# untitled.net
KiCad netlist of a schematic drawn in EAGLE
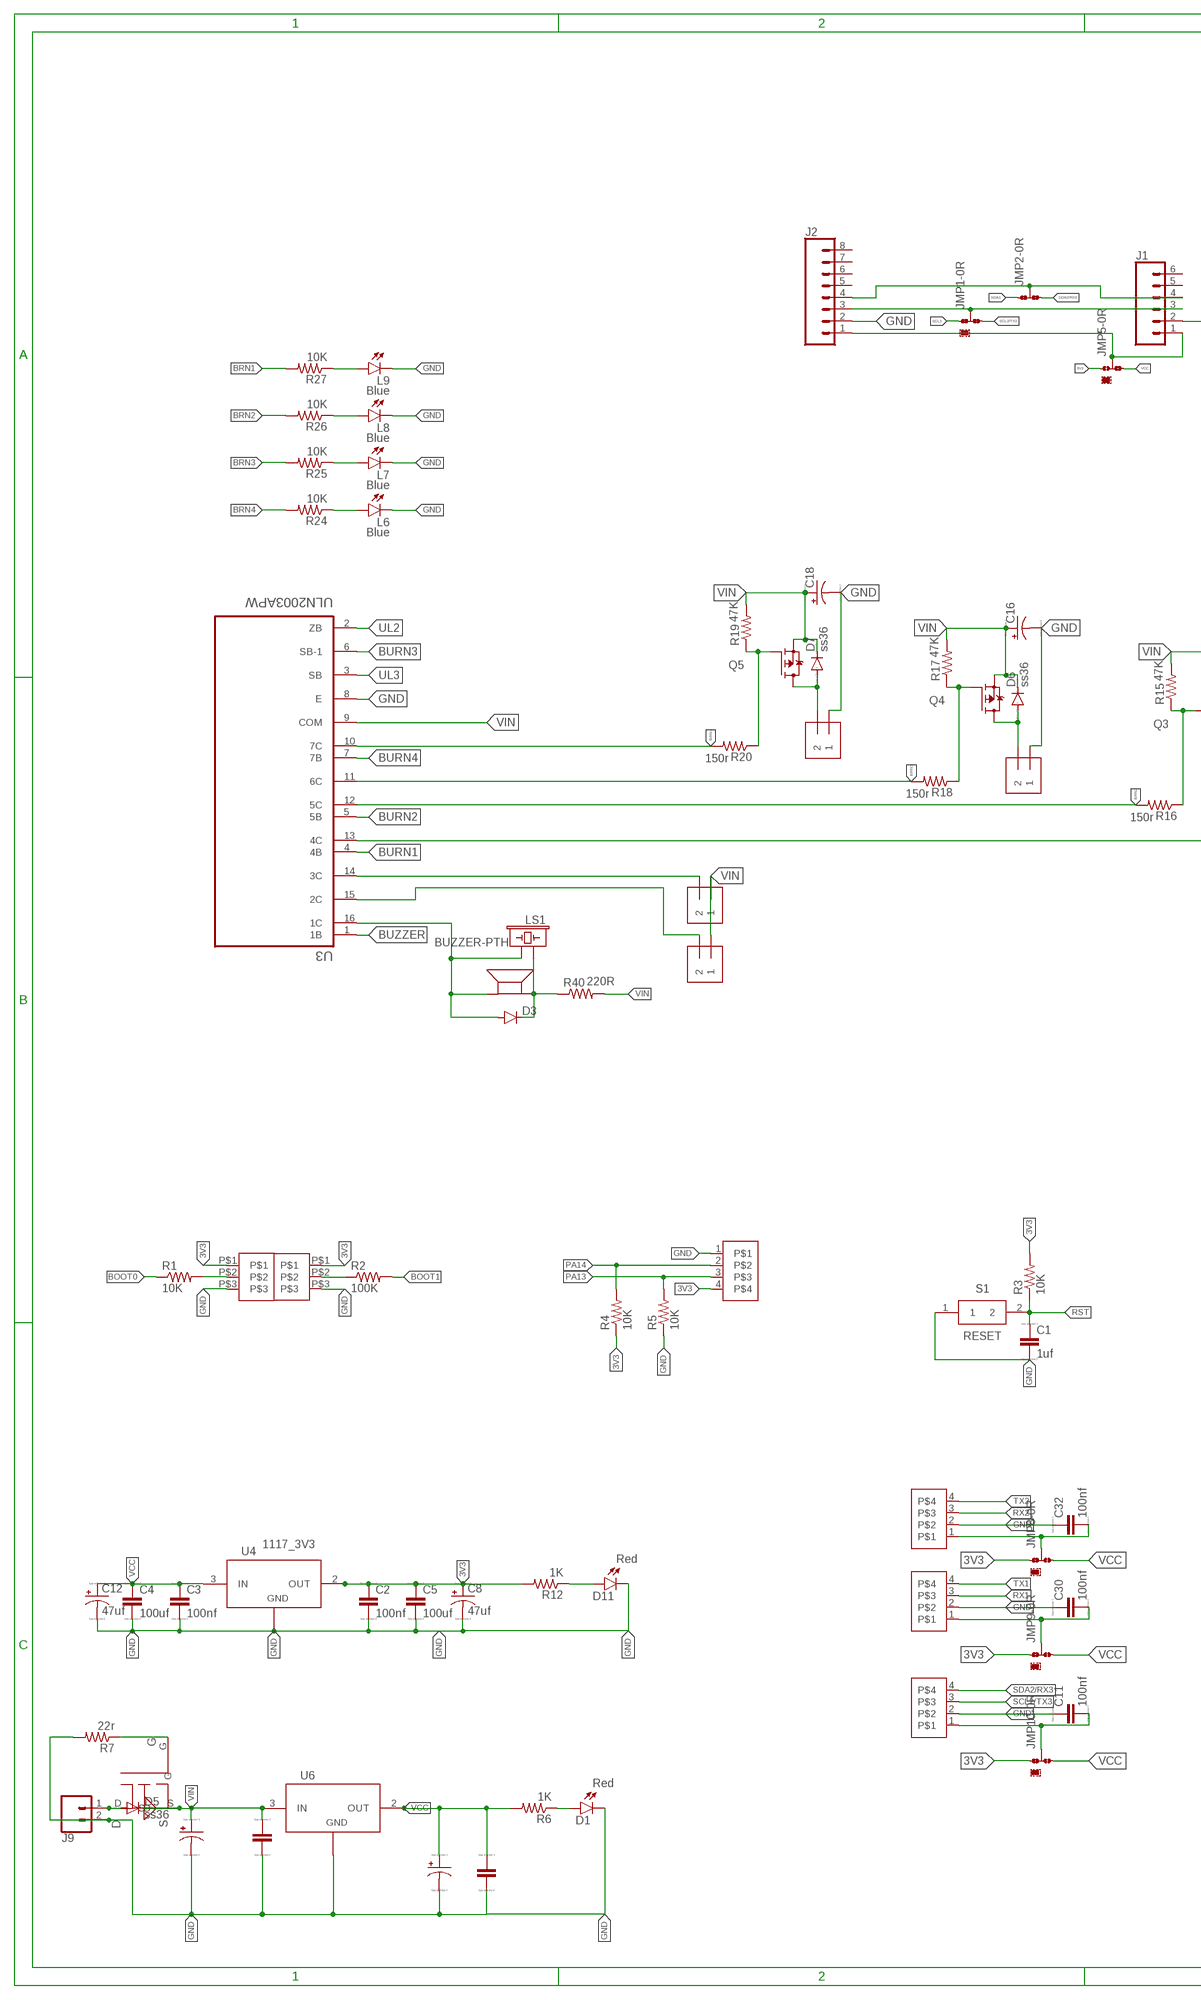
[diagram p0: schematic, sheet 1, part 1 of 2]
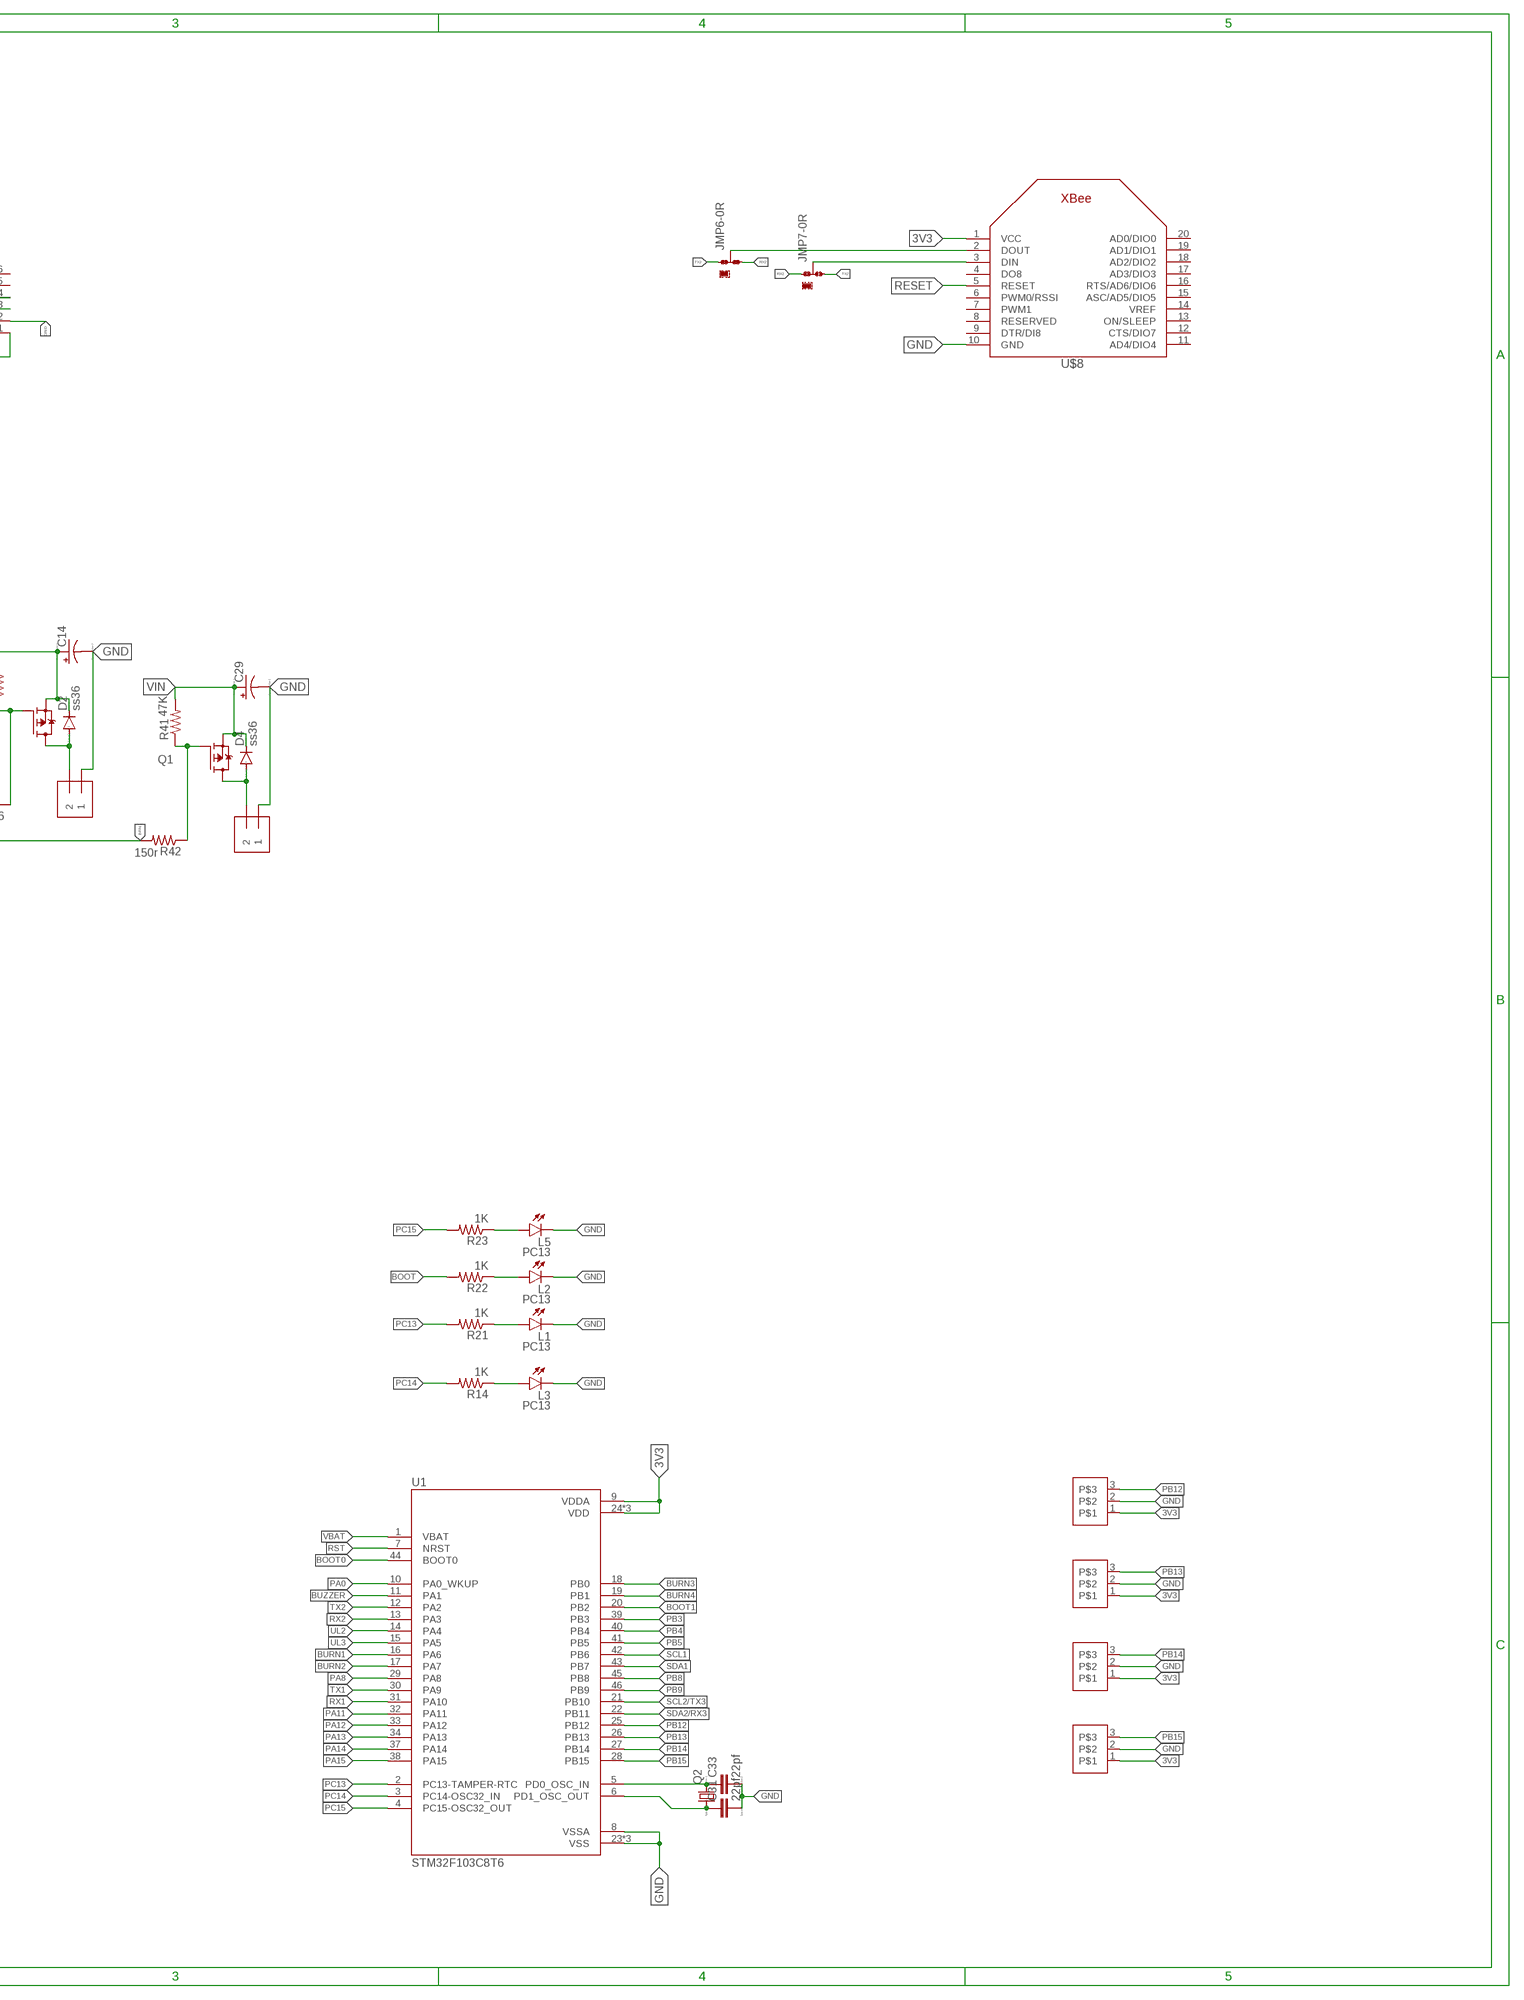
[diagram p1: schematic, sheet 1, part 2 of 2]

(export (version "E")
  (design (tool "Eeschema 10.0.6"))
  (components
    (comp (ref "C1")
      (value "1uf")
      (footprint "eagle-import:C0603")
      (libsource (lib "eagle-import") (part "CAPACITOR_CER4"))
    )
    (comp (ref "C2")
      (value "100nf")
      (footprint "eagle-import:C0603")
      (libsource (lib "eagle-import") (part "CAPACITOR_CER4"))
    )
    (comp (ref "C3")
      (value "100nf")
      (footprint "eagle-import:C0603")
      (libsource (lib "eagle-import") (part "CAPACITOR_CER4"))
    )
    (comp (ref "C4")
      (value "100uf")
      (footprint "eagle-import:C1210")
      (libsource (lib "eagle-import") (part "CAPACITOR_CER9"))
    )
    (comp (ref "C5")
      (value "100uf")
      (footprint "eagle-import:C1210")
      (libsource (lib "eagle-import") (part "CAPACITOR_CER9"))
    )
    (comp (ref "C6")
      (value "100nf")
      (footprint "eagle-import:C0603")
      (libsource (lib "eagle-import") (part "CAPACITOR_CER4"))
    )
    (comp (ref "C7")
      (value "100uf")
      (footprint "eagle-import:PANASONIC_D")
      (libsource (lib "eagle-import") (part "CAPACITOR_POLD"))
    )
    (comp (ref "C8")
      (value "47uf")
      (footprint "eagle-import:PANASONIC_C")
      (libsource (lib "eagle-import") (part "CAPACITOR_POLC"))
    )
    (comp (ref "C9")
      (value "100nf")
      (footprint "eagle-import:C0603")
      (libsource (lib "eagle-import") (part "CAPACITOR_CER4"))
    )
    (comp (ref "C10")
      (value "100uf")
      (footprint "eagle-import:PANASONIC_D")
      (libsource (lib "eagle-import") (part "CAPACITOR_POLD"))
    )
    (comp (ref "C11")
      (value "100nf")
      (footprint "eagle-import:C0603")
      (libsource (lib "eagle-import") (part "CAPACITOR_CER4"))
    )
    (comp (ref "C12")
      (value "47uf")
      (footprint "eagle-import:PANASONIC_C")
      (libsource (lib "eagle-import") (part "CAPACITOR_POLC"))
    )
    (comp (ref "C14")
      (value "CAPACITOR_POLC")
      (footprint "eagle-import:PANASONIC_C")
      (libsource (lib "eagle-import") (part "CAPACITOR_POLC"))
    )
    (comp (ref "C16")
      (value "CAPACITOR_POLC")
      (footprint "eagle-import:PANASONIC_C")
      (libsource (lib "eagle-import") (part "CAPACITOR_POLC"))
    )
    (comp (ref "C18")
      (value "CAPACITOR_POLC")
      (footprint "eagle-import:PANASONIC_C")
      (libsource (lib "eagle-import") (part "CAPACITOR_POLC"))
    )
    (comp (ref "C29")
      (value "CAPACITOR_POLC")
      (footprint "eagle-import:PANASONIC_C")
      (libsource (lib "eagle-import") (part "CAPACITOR_POLC"))
    )
    (comp (ref "C30")
      (value "100nf")
      (footprint "eagle-import:C0603")
      (libsource (lib "eagle-import") (part "CAPACITOR_CER4"))
    )
    (comp (ref "C31")
      (value "22pf")
      (footprint "eagle-import:C0603")
      (libsource (lib "eagle-import") (part "CAPACITOR_CER4"))
    )
    (comp (ref "C32")
      (value "100nf")
      (footprint "eagle-import:C0603")
      (libsource (lib "eagle-import") (part "CAPACITOR_CER4"))
    )
    (comp (ref "C33")
      (value "22pf")
      (footprint "eagle-import:C0603")
      (libsource (lib "eagle-import") (part "CAPACITOR_CER4"))
    )
    (comp (ref "D1")
      (value "Red")
      (footprint "eagle-import:0603_LED_GREEN")
      (libsource (lib "eagle-import") (part "LED0603_R"))
    )
    (comp (ref "D2")
      (value "ss36")
      (footprint "eagle-import:DO-214AC")
      (libsource (lib "eagle-import") (part "DIODEAC2"))
    )
    (comp (ref "D3")
      (value "DIODESOD")
      (footprint "eagle-import:SOD-323")
      (libsource (lib "eagle-import") (part "DIODESOD"))
    )
    (comp (ref "D4")
      (value "ss36")
      (footprint "eagle-import:DO-214AC")
      (libsource (lib "eagle-import") (part "DIODEAC2"))
    )
    (comp (ref "D5")
      (value "ss36")
      (footprint "eagle-import:DO-214AC")
      (libsource (lib "eagle-import") (part "DIODEAC2"))
    )
    (comp (ref "D6")
      (value "ss36")
      (footprint "eagle-import:DO-214AC")
      (libsource (lib "eagle-import") (part "DIODEAC2"))
    )
    (comp (ref "D7")
      (value "ss36")
      (footprint "eagle-import:DO-214AC")
      (libsource (lib "eagle-import") (part "DIODEAC2"))
    )
    (comp (ref "D11")
      (value "Red")
      (footprint "eagle-import:0603_LED_GREEN")
      (libsource (lib "eagle-import") (part "LED0603_R"))
    )
    (comp (ref "J1")
      (value "CONN_06NO_SILK_NO_POP")
      (footprint "eagle-import:1X06_NO_SILK")
      (libsource (lib "eagle-import") (part "CONN_06NO_SILK_NO_POP"))
    )
    (comp (ref "J2")
      (value "CONN_08NO_SILK_FEMALE_PTH")
      (footprint "eagle-import:1X08_NO_SILK")
      (libsource (lib "eagle-import") (part "CONN_08NO_SILK_FEMALE_PTH"))
    )
    (comp (ref "J9")
      (value "CONN_025MM")
      (footprint "eagle-import:SCREWTERMINAL-5MM-2")
      (libsource (lib "eagle-import") (part "CONN_025MM"))
    )
    (comp (ref "JMP1")
      (value "0R-JUMPA")
      (footprint "eagle-import:A0R-JMP")
      (libsource (lib "eagle-import") (part "0R-JUMPA"))
    )
    (comp (ref "JMP2")
      (value "0R-JUMPA")
      (footprint "eagle-import:A0R-JMP")
      (libsource (lib "eagle-import") (part "0R-JUMPA"))
    )
    (comp (ref "JMP5")
      (value "0R-JUMPA")
      (footprint "eagle-import:A0R-JMP")
      (libsource (lib "eagle-import") (part "0R-JUMPA"))
    )
    (comp (ref "JMP6")
      (value "0R-JUMPA")
      (footprint "eagle-import:A0R-JMP")
      (libsource (lib "eagle-import") (part "0R-JUMPA"))
    )
    (comp (ref "JMP7")
      (value "0R-JUMPA")
      (footprint "eagle-import:A0R-JMP")
      (libsource (lib "eagle-import") (part "0R-JUMPA"))
    )
    (comp (ref "JMP8")
      (value "0R-JUMPA")
      (footprint "eagle-import:A0R-JMP")
      (libsource (lib "eagle-import") (part "0R-JUMPA"))
    )
    (comp (ref "JMP9")
      (value "0R-JUMPA")
      (footprint "eagle-import:A0R-JMP")
      (libsource (lib "eagle-import") (part "0R-JUMPA"))
    )
    (comp (ref "JMP10")
      (value "0R-JUMPA")
      (footprint "eagle-import:A0R-JMP")
      (libsource (lib "eagle-import") (part "0R-JUMPA"))
    )
    (comp (ref "L1")
      (value "PC13")
      (footprint "eagle-import:0603_LED_GREEN")
      (libsource (lib "eagle-import") (part "LED0603_R"))
    )
    (comp (ref "L2")
      (value "PC13")
      (footprint "eagle-import:0603_LED_GREEN")
      (libsource (lib "eagle-import") (part "LED0603_R"))
    )
    (comp (ref "L3")
      (value "PC13")
      (footprint "eagle-import:0603_LED_GREEN")
      (libsource (lib "eagle-import") (part "LED0603_R"))
    )
    (comp (ref "L5")
      (value "PC13")
      (footprint "eagle-import:0603_LED_GREEN")
      (libsource (lib "eagle-import") (part "LED0603_R"))
    )
    (comp (ref "L6")
      (value "Blue")
      (footprint "eagle-import:0603_LED_GREEN")
      (libsource (lib "eagle-import") (part "LED0603_R"))
    )
    (comp (ref "L7")
      (value "Blue")
      (footprint "eagle-import:0603_LED_GREEN")
      (libsource (lib "eagle-import") (part "LED0603_R"))
    )
    (comp (ref "L8")
      (value "Blue")
      (footprint "eagle-import:0603_LED_GREEN")
      (libsource (lib "eagle-import") (part "LED0603_R"))
    )
    (comp (ref "L9")
      (value "Blue")
      (footprint "eagle-import:0603_LED_GREEN")
      (libsource (lib "eagle-import") (part "LED0603_R"))
    )
    (comp (ref "LS1")
      (value "BUZZER-PTH")
      (footprint "eagle-import:BUZZER-12MM")
      (libsource (lib "eagle-import") (part "BUZZER-PTH"))
    )
    (comp (ref "Q1")
      (value "FDD4141TO252")
      (footprint "eagle-import:TO252")
      (libsource (lib "eagle-import") (part "FDD4141TO252"))
    )
    (comp (ref "Q2")
      (value "CRYSTALHC49U-V")
      (footprint "eagle-import:HC49U-V")
      (libsource (lib "eagle-import") (part "CRYSTALHC49U-V"))
    )
    (comp (ref "Q3")
      (value "FDD4141TO252")
      (footprint "eagle-import:TO252")
      (libsource (lib "eagle-import") (part "FDD4141TO252"))
    )
    (comp (ref "Q4")
      (value "FDD4141TO252")
      (footprint "eagle-import:TO252")
      (libsource (lib "eagle-import") (part "FDD4141TO252"))
    )
    (comp (ref "Q5")
      (value "FDD4141TO252")
      (footprint "eagle-import:TO252")
      (libsource (lib "eagle-import") (part "FDD4141TO252"))
    )
    (comp (ref "Q6")
      (value "AON7401")
      (footprint "eagle-import:DFN-8_3X3")
      (libsource (lib "eagle-import") (part "AON7401"))
    )
    (comp (ref "R1")
      (value "10K")
      (footprint "eagle-import:R0603")
      (libsource (lib "eagle-import") (part "RESISTOR0603"))
    )
    (comp (ref "R2")
      (value "100K")
      (footprint "eagle-import:R0603")
      (libsource (lib "eagle-import") (part "RESISTOR0603"))
    )
    (comp (ref "R3")
      (value "10K")
      (footprint "eagle-import:R0603")
      (libsource (lib "eagle-import") (part "RESISTOR0603"))
    )
    (comp (ref "R4")
      (value "10K")
      (footprint "eagle-import:R0603")
      (libsource (lib "eagle-import") (part "RESISTOR0603"))
    )
    (comp (ref "R5")
      (value "10K")
      (footprint "eagle-import:R0603")
      (libsource (lib "eagle-import") (part "RESISTOR0603"))
    )
    (comp (ref "R6")
      (value "1K")
      (footprint "eagle-import:R0603")
      (libsource (lib "eagle-import") (part "RESISTOR0603"))
    )
    (comp (ref "R7")
      (value "22r")
      (footprint "eagle-import:R0603")
      (libsource (lib "eagle-import") (part "RESISTOR0603"))
    )
    (comp (ref "R12")
      (value "1K")
      (footprint "eagle-import:R0603")
      (libsource (lib "eagle-import") (part "RESISTOR0603"))
    )
    (comp (ref "R14")
      (value "1K")
      (footprint "eagle-import:R0603")
      (libsource (lib "eagle-import") (part "RESISTOR0603"))
    )
    (comp (ref "R15")
      (value "47K")
      (footprint "eagle-import:R0603")
      (libsource (lib "eagle-import") (part "RESISTOR0603"))
    )
    (comp (ref "R16")
      (value "150r")
      (footprint "eagle-import:R0603")
      (libsource (lib "eagle-import") (part "RESISTOR0603"))
    )
    (comp (ref "R17")
      (value "47K")
      (footprint "eagle-import:R0603")
      (libsource (lib "eagle-import") (part "RESISTOR0603"))
    )
    (comp (ref "R18")
      (value "150r")
      (footprint "eagle-import:R0603")
      (libsource (lib "eagle-import") (part "RESISTOR0603"))
    )
    (comp (ref "R19")
      (value "47K")
      (footprint "eagle-import:R0603")
      (libsource (lib "eagle-import") (part "RESISTOR0603"))
    )
    (comp (ref "R20")
      (value "150r")
      (footprint "eagle-import:R0603")
      (libsource (lib "eagle-import") (part "RESISTOR0603"))
    )
    (comp (ref "R21")
      (value "1K")
      (footprint "eagle-import:R0603")
      (libsource (lib "eagle-import") (part "RESISTOR0603"))
    )
    (comp (ref "R22")
      (value "1K")
      (footprint "eagle-import:R0603")
      (libsource (lib "eagle-import") (part "RESISTOR0603"))
    )
    (comp (ref "R23")
      (value "1K")
      (footprint "eagle-import:R0603")
      (libsource (lib "eagle-import") (part "RESISTOR0603"))
    )
    (comp (ref "R24")
      (value "10K")
      (footprint "eagle-import:R0603")
      (libsource (lib "eagle-import") (part "RESISTOR0603"))
    )
    (comp (ref "R25")
      (value "10K")
      (footprint "eagle-import:R0603")
      (libsource (lib "eagle-import") (part "RESISTOR0603"))
    )
    (comp (ref "R26")
      (value "10K")
      (footprint "eagle-import:R0603")
      (libsource (lib "eagle-import") (part "RESISTOR0603"))
    )
    (comp (ref "R27")
      (value "10K")
      (footprint "eagle-import:R0603")
      (libsource (lib "eagle-import") (part "RESISTOR0603"))
    )
    (comp (ref "R40")
      (value "220R")
      (footprint "eagle-import:R0603")
      (libsource (lib "eagle-import") (part "RESISTOR0603"))
    )
    (comp (ref "R41")
      (value "47K")
      (footprint "eagle-import:R0603")
      (libsource (lib "eagle-import") (part "RESISTOR0603"))
    )
    (comp (ref "R42")
      (value "150r")
      (footprint "eagle-import:R0603")
      (libsource (lib "eagle-import") (part "RESISTOR0603"))
    )
    (comp (ref "S1")
      (value "RESET")
      (footprint "eagle-import:SKRK")
      (fields (field (name "MF") "ALPS") (field (name "MP") "SKRKAEE010"))
      (libsource (lib "eagle-import") (part "SKRKAEE010"))
    )
    (comp (ref "U$1")
      (value "FML_1X32MM")
      (footprint "eagle-import:1X3_2MM")
      (libsource (lib "eagle-import") (part "FML_1X32MM"))
    )
    (comp (ref "U$2")
      (value "FML_1X32MM")
      (footprint "eagle-import:1X3_2MM")
      (libsource (lib "eagle-import") (part "FML_1X32MM"))
    )
    (comp (ref "U$3")
      (value "FML_1X4")
      (footprint "eagle-import:HDRVR4W64P254_1X4_1016X240X800B")
      (libsource (lib "eagle-import") (part "FML_1X4"))
    )
    (comp (ref "U$4")
      (value "1X2")
      (footprint "eagle-import:1X2")
      (libsource (lib "eagle-import") (part "1X2"))
    )
    (comp (ref "U$5")
      (value "1X2")
      (footprint "eagle-import:1X2")
      (libsource (lib "eagle-import") (part "1X2"))
    )
    (comp (ref "U$6")
      (value "1X2")
      (footprint "eagle-import:1X2")
      (libsource (lib "eagle-import") (part "1X2"))
    )
    (comp (ref "U$7")
      (value "FML_1X4")
      (footprint "eagle-import:HDRVR4W64P254_1X4_1016X240X800B")
      (libsource (lib "eagle-import") (part "FML_1X4"))
    )
    (comp (ref "U$8")
      (value "XBEE")
      (footprint "eagle-import:XBEE")
      (libsource (lib "eagle-import") (part "XBEE"))
    )
    (comp (ref "U$9")
      (value "Z_STOP")
      (footprint "eagle-import:HDRVR3W64P254_1X3_762X240X800B")
      (libsource (lib "eagle-import") (part "FML_1X3"))
    )
    (comp (ref "U$11")
      (value "FML_1X4")
      (footprint "eagle-import:HDRVR4W64P254_1X4_1016X240X800B")
      (libsource (lib "eagle-import") (part "FML_1X4"))
    )
    (comp (ref "U$12")
      (value "FML_1X4")
      (footprint "eagle-import:HDRVR4W64P254_1X4_1016X240X800B")
      (libsource (lib "eagle-import") (part "FML_1X4"))
    )
    (comp (ref "U$13")
      (value "Z_STOP")
      (footprint "eagle-import:HDRVR3W64P254_1X3_762X240X800B")
      (libsource (lib "eagle-import") (part "FML_1X3"))
    )
    (comp (ref "U$14")
      (value "Y_STOP")
      (footprint "eagle-import:HDRVR3W64P254_1X3_762X240X800B")
      (libsource (lib "eagle-import") (part "FML_1X3"))
    )
    (comp (ref "U$15")
      (value "X_STOP")
      (footprint "eagle-import:HDRVR3W64P254_1X3_762X240X800B")
      (libsource (lib "eagle-import") (part "FML_1X3"))
    )
    (comp (ref "U$19")
      (value "7.5X7.5_BUZZER")
      (footprint "eagle-import:SMD_7.5_BUZZER")
      (libsource (lib "eagle-import") (part "7.5X7.5_BUZZER"))
    )
    (comp (ref "U$20")
      (value "1X2")
      (footprint "eagle-import:1X2")
      (libsource (lib "eagle-import") (part "1X2"))
    )
    (comp (ref "U$21")
      (value "1X2")
      (footprint "eagle-import:1X2")
      (libsource (lib "eagle-import") (part "1X2"))
    )
    (comp (ref "U$22")
      (value "1X2")
      (footprint "eagle-import:1X2")
      (libsource (lib "eagle-import") (part "1X2"))
    )
    (comp (ref "U1")
      (value "STM32F103C8T6")
      (footprint "eagle-import:QFP50P900X900X160-48N")
      (fields (field (name "MF") "STMicroelectronics"))
      (libsource (lib "eagle-import") (part "STM32F103C8T6"))
    )
    (comp (ref "U3")
      (value "ULN2003APW")
      (footprint "eagle-import:SOP65P640X120-16N")
      (fields (field (name "MF") "Texas Instruments"))
      (libsource (lib "eagle-import") (part "ULN2003APW"))
    )
    (comp (ref "U4")
      (value "1117_3V3")
      (footprint "eagle-import:SOT-223")
      (fields
        (field (name "DIGIKEY_PART_NUMBER") "NCP1117ST33T3GOSTR-ND")
        (field (name "MANUFACTURER") "ON Semiconductor")
        (field (name "MPN") "NCP1117ST33T3G")
        (field (name "CREATED_BY") "PCBLayout.com")
      )
      (libsource (lib "eagle-import") (part "NCP1117ST33T3G"))
    )
    (comp (ref "U6")
      (value "1117_3V3")
      (footprint "eagle-import:SOT-223")
      (fields
        (field (name "DIGIKEY_PART_NUMBER") "NCP1117ST33T3GOSTR-ND")
        (field (name "MANUFACTURER") "ON Semiconductor")
        (field (name "MPN") "NCP1117ST33T3G")
        (field (name "CREATED_BY") "PCBLayout.com")
      )
      (libsource (lib "eagle-import") (part "NCP1117ST33T3G"))
    )
  )
  (nets
    (net (code "1") (name "3V3") (class "Default")
      (node (ref "C2") (pin "1") (pinfunction "1_1") (pintype "passive"))
      (node (ref "C5") (pin "1") (pinfunction "1_1") (pintype "passive"))
      (node (ref "C8") (pin "+") (pinfunction "+_+") (pintype "passive"))
      (node (ref "JMP10") (pin "1") (pinfunction "1_1") (pintype "passive"))
      (node (ref "JMP5") (pin "1") (pinfunction "1_1") (pintype "passive"))
      (node (ref "JMP8") (pin "1") (pinfunction "1_1") (pintype "passive"))
      (node (ref "JMP9") (pin "1") (pinfunction "1_1") (pintype "passive"))
      (node (ref "R12") (pin "2") (pinfunction "2_2") (pintype "passive"))
      (node (ref "R3") (pin "2") (pinfunction "2_2") (pintype "passive"))
      (node (ref "R4") (pin "1") (pinfunction "1_1") (pintype "passive"))
      (node (ref "U$1") (pin "P$1") (pinfunction "P$1_P$1") (pintype "bidirectional"))
      (node (ref "U$13") (pin "1") (pinfunction "P$1_1") (pintype "bidirectional"))
      (node (ref "U$14") (pin "1") (pinfunction "P$1_1") (pintype "bidirectional"))
      (node (ref "U$15") (pin "1") (pinfunction "P$1_1") (pintype "bidirectional"))
      (node (ref "U$2") (pin "P$1") (pinfunction "P$1_P$1") (pintype "bidirectional"))
      (node (ref "U$3") (pin "4") (pinfunction "P$4_4") (pintype "bidirectional"))
      (node (ref "U$8") (pin "1") (pinfunction "VCC_1") (pintype "power_in"))
      (node (ref "U$9") (pin "1") (pinfunction "P$1_1") (pintype "bidirectional"))
      (node (ref "U1") (pin "24") (pinfunction "VDD_24") (pintype "power_in"))
      (node (ref "U1") (pin "36") (pinfunction "VDD_36") (pintype "power_in"))
      (node (ref "U1") (pin "48") (pinfunction "VDD_48") (pintype "power_in"))
      (node (ref "U1") (pin "9") (pinfunction "VDDA_9") (pintype "power_in"))
      (node (ref "U4") (pin "2") (pinfunction "OUT_2") (pintype "output"))
      (node (ref "U4") (pin "4") (pinfunction "4_4") (pintype "passive"))
    )
    (net (code "2") (name "BOOT") (class "Default")
      (node (ref "R1") (pin "2") (pinfunction "2_2") (pintype "passive"))
      (node (ref "R22") (pin "2") (pinfunction "2_2") (pintype "passive"))
      (node (ref "U$2") (pin "P$2") (pinfunction "P$2_P$2") (pintype "bidirectional"))
    )
    (net (code "3") (name "BOOT0") (class "Default")
      (node (ref "R1") (pin "1") (pinfunction "1_1") (pintype "passive"))
      (node (ref "U1") (pin "44") (pinfunction "BOOT0_44") (pintype "input"))
    )
    (net (code "4") (name "BOOT1") (class "Default")
      (node (ref "R2") (pin "2") (pinfunction "2_2") (pintype "passive"))
      (node (ref "U1") (pin "20") (pinfunction "PB2_20") (pintype "bidirectional"))
    )
    (net (code "5") (name "BRN1") (class "Default")
      (node (ref "R27") (pin "2") (pinfunction "2_2") (pintype "passive"))
      (node (ref "R42") (pin "2") (pinfunction "2_2") (pintype "passive"))
      (node (ref "U3") (pin "13") (pinfunction "4C_13") (pintype "bidirectional"))
    )
    (net (code "6") (name "BRN2") (class "Default")
      (node (ref "R16") (pin "2") (pinfunction "2_2") (pintype "passive"))
      (node (ref "R26") (pin "2") (pinfunction "2_2") (pintype "passive"))
      (node (ref "U3") (pin "12") (pinfunction "5C_12") (pintype "bidirectional"))
    )
    (net (code "7") (name "BRN3") (class "Default")
      (node (ref "R18") (pin "2") (pinfunction "2_2") (pintype "passive"))
      (node (ref "R25") (pin "2") (pinfunction "2_2") (pintype "passive"))
      (node (ref "U3") (pin "11") (pinfunction "6C_11") (pintype "bidirectional"))
    )
    (net (code "8") (name "BRN4") (class "Default")
      (node (ref "R20") (pin "2") (pinfunction "2_2") (pintype "passive"))
      (node (ref "R24") (pin "2") (pinfunction "2_2") (pintype "passive"))
      (node (ref "U3") (pin "10") (pinfunction "7C_10") (pintype "bidirectional"))
    )
    (net (code "9") (name "BURN1") (class "Default")
      (node (ref "U1") (pin "16") (pinfunction "PA6_16") (pintype "bidirectional"))
      (node (ref "U3") (pin "4") (pinfunction "4B_4") (pintype "bidirectional"))
    )
    (net (code "10") (name "BURN2") (class "Default")
      (node (ref "U1") (pin "17") (pinfunction "PA7_17") (pintype "bidirectional"))
      (node (ref "U3") (pin "5") (pinfunction "5B_5") (pintype "bidirectional"))
    )
    (net (code "11") (name "BURN3") (class "Default")
      (node (ref "U1") (pin "18") (pinfunction "PB0_18") (pintype "bidirectional"))
      (node (ref "U3") (pin "6") (pinfunction "SB-1_6") (pintype "bidirectional"))
    )
    (net (code "12") (name "BURN4") (class "Default")
      (node (ref "U1") (pin "19") (pinfunction "PB1_19") (pintype "bidirectional"))
      (node (ref "U3") (pin "7") (pinfunction "7B_7") (pintype "bidirectional"))
    )
    (net (code "13") (name "BUZZER") (class "Default")
      (node (ref "U1") (pin "11") (pinfunction "PA1_11") (pintype "bidirectional"))
      (node (ref "U3") (pin "1") (pinfunction "1B_1") (pintype "bidirectional"))
    )
    (net (code "14") (name "GND") (class "Default")
      (node (ref "C1") (pin "2") (pinfunction "2_2") (pintype "passive"))
      (node (ref "C10") (pin "-") (pinfunction "-_-") (pintype "passive"))
      (node (ref "C11") (pin "1") (pinfunction "1_1") (pintype "passive"))
      (node (ref "C12") (pin "-") (pinfunction "-_-") (pintype "passive"))
      (node (ref "C14") (pin "-") (pinfunction "-_-") (pintype "passive"))
      (node (ref "C16") (pin "-") (pinfunction "-_-") (pintype "passive"))
      (node (ref "C18") (pin "-") (pinfunction "-_-") (pintype "passive"))
      (node (ref "C2") (pin "2") (pinfunction "2_2") (pintype "passive"))
      (node (ref "C29") (pin "-") (pinfunction "-_-") (pintype "passive"))
      (node (ref "C3") (pin "2") (pinfunction "2_2") (pintype "passive"))
      (node (ref "C30") (pin "1") (pinfunction "1_1") (pintype "passive"))
      (node (ref "C31") (pin "2") (pinfunction "2_2") (pintype "passive"))
      (node (ref "C32") (pin "1") (pinfunction "1_1") (pintype "passive"))
      (node (ref "C33") (pin "2") (pinfunction "2_2") (pintype "passive"))
      (node (ref "C4") (pin "2") (pinfunction "2_2") (pintype "passive"))
      (node (ref "C5") (pin "2") (pinfunction "2_2") (pintype "passive"))
      (node (ref "C6") (pin "2") (pinfunction "2_2") (pintype "passive"))
      (node (ref "C7") (pin "-") (pinfunction "-_-") (pintype "passive"))
      (node (ref "C8") (pin "-") (pinfunction "-_-") (pintype "passive"))
      (node (ref "C9") (pin "2") (pinfunction "2_2") (pintype "passive"))
      (node (ref "D1") (pin "C") (pinfunction "C_C") (pintype "passive"))
      (node (ref "D11") (pin "C") (pinfunction "C_C") (pintype "passive"))
      (node (ref "J1") (pin "2") (pinfunction "2_2") (pintype "passive"))
      (node (ref "J2") (pin "2") (pinfunction "2_2") (pintype "passive"))
      (node (ref "J9") (pin "2") (pinfunction "2_2") (pintype "passive"))
      (node (ref "L1") (pin "C") (pinfunction "C_C") (pintype "passive"))
      (node (ref "L2") (pin "C") (pinfunction "C_C") (pintype "passive"))
      (node (ref "L3") (pin "C") (pinfunction "C_C") (pintype "passive"))
      (node (ref "L5") (pin "C") (pinfunction "C_C") (pintype "passive"))
      (node (ref "L6") (pin "C") (pinfunction "C_C") (pintype "passive"))
      (node (ref "L7") (pin "C") (pinfunction "C_C") (pintype "passive"))
      (node (ref "L8") (pin "C") (pinfunction "C_C") (pintype "passive"))
      (node (ref "L9") (pin "C") (pinfunction "C_C") (pintype "passive"))
      (node (ref "R5") (pin "1") (pinfunction "1_1") (pintype "passive"))
      (node (ref "R7") (pin "2") (pinfunction "2_2") (pintype "passive"))
      (node (ref "S1") (pin "1") (pinfunction "1_1") (pintype "passive"))
      (node (ref "U$1") (pin "P$3") (pinfunction "P$3_P$3") (pintype "bidirectional"))
      (node (ref "U$11") (pin "2") (pinfunction "P$2_2") (pintype "bidirectional"))
      (node (ref "U$12") (pin "2") (pinfunction "P$2_2") (pintype "bidirectional"))
      (node (ref "U$13") (pin "2") (pinfunction "P$2_2") (pintype "bidirectional"))
      (node (ref "U$14") (pin "2") (pinfunction "P$2_2") (pintype "bidirectional"))
      (node (ref "U$15") (pin "2") (pinfunction "P$2_2") (pintype "bidirectional"))
      (node (ref "U$2") (pin "P$3") (pinfunction "P$3_P$3") (pintype "bidirectional"))
      (node (ref "U$21") (pin "P$1") (pinfunction "1_P$1") (pintype "passive"))
      (node (ref "U$3") (pin "1") (pinfunction "P$1_1") (pintype "bidirectional"))
      (node (ref "U$4") (pin "P$1") (pinfunction "1_P$1") (pintype "passive"))
      (node (ref "U$5") (pin "P$1") (pinfunction "1_P$1") (pintype "passive"))
      (node (ref "U$6") (pin "P$1") (pinfunction "1_P$1") (pintype "passive"))
      (node (ref "U$7") (pin "2") (pinfunction "P$2_2") (pintype "bidirectional"))
      (node (ref "U$8") (pin "10") (pinfunction "GND_10") (pintype "power_in"))
      (node (ref "U$9") (pin "2") (pinfunction "P$2_2") (pintype "bidirectional"))
      (node (ref "U1") (pin "23") (pinfunction "VSS_23") (pintype "power_in"))
      (node (ref "U1") (pin "35") (pinfunction "VSS_35") (pintype "power_in"))
      (node (ref "U1") (pin "47") (pinfunction "VSS_47") (pintype "power_in"))
      (node (ref "U1") (pin "8") (pinfunction "VSSA_8") (pintype "power_in"))
      (node (ref "U3") (pin "8") (pinfunction "E_8") (pintype "bidirectional"))
      (node (ref "U4") (pin "1") (pinfunction "ADJ/GND_1") (pintype "power_in"))
      (node (ref "U6") (pin "1") (pinfunction "ADJ/GND_1") (pintype "power_in"))
    )
    (net (code "15") (name "Net-(D1-PadA)") (class "Default")
      (node (ref "D1") (pin "A") (pinfunction "A_A") (pintype "passive"))
      (node (ref "R6") (pin "1") (pinfunction "1_1") (pintype "passive"))
    )
    (net (code "16") (name "Net-(D5-PadA)") (class "Default")
      (node (ref "D5") (pin "A") (pinfunction "A_A") (pintype "passive"))
      (node (ref "J9") (pin "1") (pinfunction "1_1") (pintype "passive"))
      (node (ref "Q6") (pin "D") (pinfunction "D_D") (pintype "bidirectional"))
    )
    (net (code "17") (name "Net-(D11-PadA)") (class "Default")
      (node (ref "D11") (pin "A") (pinfunction "A_A") (pintype "passive"))
      (node (ref "R12") (pin "1") (pinfunction "1_1") (pintype "passive"))
    )
    (net (code "18") (name "Net-(J1-Pad1)") (class "Default")
      (node (ref "J1") (pin "1") (pinfunction "1_1") (pintype "passive"))
      (node (ref "J2") (pin "1") (pinfunction "1_1") (pintype "passive"))
      (node (ref "JMP5") (pin "2") (pinfunction "2_2") (pintype "passive"))
    )
    (net (code "19") (name "Net-(J1-Pad3)") (class "Default")
      (node (ref "J1") (pin "3") (pinfunction "3_3") (pintype "passive"))
      (node (ref "J2") (pin "3") (pinfunction "3_3") (pintype "passive"))
      (node (ref "JMP1") (pin "2") (pinfunction "2_2") (pintype "passive"))
    )
    (net (code "20") (name "Net-(J1-Pad4)") (class "Default")
      (node (ref "J1") (pin "4") (pinfunction "4_4") (pintype "passive"))
      (node (ref "J2") (pin "4") (pinfunction "4_4") (pintype "passive"))
      (node (ref "JMP2") (pin "2") (pinfunction "2_2") (pintype "passive"))
    )
    (net (code "21") (name "Net-(L1-PadA)") (class "Default")
      (node (ref "L1") (pin "A") (pinfunction "A_A") (pintype "passive"))
      (node (ref "R21") (pin "1") (pinfunction "1_1") (pintype "passive"))
    )
    (net (code "22") (name "Net-(L2-PadA)") (class "Default")
      (node (ref "L2") (pin "A") (pinfunction "A_A") (pintype "passive"))
      (node (ref "R22") (pin "1") (pinfunction "1_1") (pintype "passive"))
    )
    (net (code "23") (name "Net-(L3-PadA)") (class "Default")
      (node (ref "L3") (pin "A") (pinfunction "A_A") (pintype "passive"))
      (node (ref "R14") (pin "1") (pinfunction "1_1") (pintype "passive"))
    )
    (net (code "24") (name "Net-(L5-PadA)") (class "Default")
      (node (ref "L5") (pin "A") (pinfunction "A_A") (pintype "passive"))
      (node (ref "R23") (pin "1") (pinfunction "1_1") (pintype "passive"))
    )
    (net (code "25") (name "Net-(L6-PadA)") (class "Default")
      (node (ref "L6") (pin "A") (pinfunction "A_A") (pintype "passive"))
      (node (ref "R24") (pin "1") (pinfunction "1_1") (pintype "passive"))
    )
    (net (code "26") (name "Net-(L7-PadA)") (class "Default")
      (node (ref "L7") (pin "A") (pinfunction "A_A") (pintype "passive"))
      (node (ref "R25") (pin "1") (pinfunction "1_1") (pintype "passive"))
    )
    (net (code "27") (name "Net-(L8-PadA)") (class "Default")
      (node (ref "L8") (pin "A") (pinfunction "A_A") (pintype "passive"))
      (node (ref "R26") (pin "1") (pinfunction "1_1") (pintype "passive"))
    )
    (net (code "28") (name "Net-(L9-PadA)") (class "Default")
      (node (ref "L9") (pin "A") (pinfunction "A_A") (pintype "passive"))
      (node (ref "R27") (pin "1") (pinfunction "1_1") (pintype "passive"))
    )
    (net (code "29") (name "Net-(LS1-1)") (class "Default")
      (node (ref "D3") (pin "C") (pinfunction "C_C") (pintype "passive"))
      (node (ref "LS1") (pin "+") (pinfunction "1_+") (pintype "passive"))
      (node (ref "R40") (pin "1") (pinfunction "1_1") (pintype "passive"))
      (node (ref "U$19") (pin "+") (pinfunction "+_+") (pintype "bidirectional"))
    )
    (net (code "30") (name "Net-(LS1-2)") (class "Default")
      (node (ref "D3") (pin "A") (pinfunction "A_A") (pintype "passive"))
      (node (ref "LS1") (pin "-") (pinfunction "2_-") (pintype "passive"))
      (node (ref "U$19") (pin "-") (pinfunction "-_-") (pintype "bidirectional"))
      (node (ref "U3") (pin "16") (pinfunction "1C_16") (pintype "bidirectional"))
    )
    (net (code "31") (name "Net-(Q1-D)") (class "Default")
      (node (ref "D4") (pin "A") (pinfunction "A_A") (pintype "passive"))
      (node (ref "Q1") (pin "3") (pinfunction "D_3") (pintype "passive"))
      (node (ref "U$21") (pin "P$2") (pinfunction "2_P$2") (pintype "passive"))
    )
    (net (code "32") (name "Net-(Q1-G)") (class "Default")
      (node (ref "Q1") (pin "1") (pinfunction "G_1") (pintype "passive"))
      (node (ref "R41") (pin "1") (pinfunction "1_1") (pintype "passive"))
      (node (ref "R42") (pin "1") (pinfunction "1_1") (pintype "passive"))
    )
    (net (code "33") (name "Net-(Q3-D)") (class "Default")
      (node (ref "D2") (pin "A") (pinfunction "A_A") (pintype "passive"))
      (node (ref "Q3") (pin "3") (pinfunction "D_3") (pintype "passive"))
      (node (ref "U$4") (pin "P$2") (pinfunction "2_P$2") (pintype "passive"))
    )
    (net (code "34") (name "Net-(Q3-G)") (class "Default")
      (node (ref "Q3") (pin "1") (pinfunction "G_1") (pintype "passive"))
      (node (ref "R15") (pin "1") (pinfunction "1_1") (pintype "passive"))
      (node (ref "R16") (pin "1") (pinfunction "1_1") (pintype "passive"))
    )
    (net (code "35") (name "Net-(Q4-D)") (class "Default")
      (node (ref "D6") (pin "A") (pinfunction "A_A") (pintype "passive"))
      (node (ref "Q4") (pin "3") (pinfunction "D_3") (pintype "passive"))
      (node (ref "U$5") (pin "P$2") (pinfunction "2_P$2") (pintype "passive"))
    )
    (net (code "36") (name "Net-(Q4-G)") (class "Default")
      (node (ref "Q4") (pin "1") (pinfunction "G_1") (pintype "passive"))
      (node (ref "R17") (pin "1") (pinfunction "1_1") (pintype "passive"))
      (node (ref "R18") (pin "1") (pinfunction "1_1") (pintype "passive"))
    )
    (net (code "37") (name "Net-(Q5-D)") (class "Default")
      (node (ref "D7") (pin "A") (pinfunction "A_A") (pintype "passive"))
      (node (ref "Q5") (pin "3") (pinfunction "D_3") (pintype "passive"))
      (node (ref "U$6") (pin "P$2") (pinfunction "2_P$2") (pintype "passive"))
    )
    (net (code "38") (name "Net-(Q5-G)") (class "Default")
      (node (ref "Q5") (pin "1") (pinfunction "G_1") (pintype "passive"))
      (node (ref "R19") (pin "1") (pinfunction "1_1") (pintype "passive"))
      (node (ref "R20") (pin "1") (pinfunction "1_1") (pintype "passive"))
    )
    (net (code "39") (name "Net-(Q6-PadG)") (class "Default")
      (node (ref "Q6") (pin "G") (pinfunction "G_G") (pintype "bidirectional"))
      (node (ref "R7") (pin "1") (pinfunction "1_1") (pintype "passive"))
    )
    (net (code "40") (name "Net-(R2-Pad1)") (class "Default")
      (node (ref "R2") (pin "1") (pinfunction "1_1") (pintype "passive"))
      (node (ref "U$1") (pin "P$2") (pinfunction "P$2_P$2") (pintype "bidirectional"))
    )
    (net (code "41") (name "Net-(U$7-P$1)") (class "Default")
      (node (ref "C11") (pin "2") (pinfunction "2_2") (pintype "passive"))
      (node (ref "JMP10") (pin "2") (pinfunction "2_2") (pintype "passive"))
      (node (ref "U$7") (pin "1") (pinfunction "P$1_1") (pintype "bidirectional"))
    )
    (net (code "42") (name "Net-(U$8-DIN)") (class "Default")
      (node (ref "JMP7") (pin "2") (pinfunction "2_2") (pintype "passive"))
      (node (ref "U$8") (pin "3") (pinfunction "DIN_3") (pintype "input"))
    )
    (net (code "43") (name "Net-(U$8-DOUT)") (class "Default")
      (node (ref "JMP6") (pin "2") (pinfunction "2_2") (pintype "passive"))
      (node (ref "U$8") (pin "2") (pinfunction "DOUT_2") (pintype "output"))
    )
    (net (code "44") (name "Net-(U$11-P$1)") (class "Default")
      (node (ref "C32") (pin "2") (pinfunction "2_2") (pintype "passive"))
      (node (ref "JMP8") (pin "2") (pinfunction "2_2") (pintype "passive"))
      (node (ref "U$11") (pin "1") (pinfunction "P$1_1") (pintype "bidirectional"))
    )
    (net (code "45") (name "Net-(U$12-P$1)") (class "Default")
      (node (ref "C30") (pin "2") (pinfunction "2_2") (pintype "passive"))
      (node (ref "JMP9") (pin "2") (pinfunction "2_2") (pintype "passive"))
      (node (ref "U$12") (pin "1") (pinfunction "P$1_1") (pintype "bidirectional"))
    )
    (net (code "46") (name "Net-(U$20-2)") (class "Default")
      (node (ref "U$20") (pin "P$2") (pinfunction "2_P$2") (pintype "passive"))
      (node (ref "U3") (pin "15") (pinfunction "2C_15") (pintype "bidirectional"))
    )
    (net (code "47") (name "Net-(U$22-2)") (class "Default")
      (node (ref "U$22") (pin "P$2") (pinfunction "2_P$2") (pintype "passive"))
      (node (ref "U3") (pin "14") (pinfunction "3C_14") (pintype "bidirectional"))
    )
    (net (code "48") (name "Net-(U1-PD0_OSC_IN)") (class "Default")
      (node (ref "C33") (pin "1") (pinfunction "1_1") (pintype "passive"))
      (node (ref "Q2") (pin "2") (pinfunction "2_2") (pintype "passive"))
      (node (ref "U1") (pin "5") (pinfunction "PD0_OSC_IN_5") (pintype "bidirectional"))
    )
    (net (code "49") (name "Net-(U1-PD1_OSC_OUT)") (class "Default")
      (node (ref "C31") (pin "1") (pinfunction "1_1") (pintype "passive"))
      (node (ref "Q2") (pin "1") (pinfunction "1_1") (pintype "passive"))
      (node (ref "U1") (pin "6") (pinfunction "PD1_OSC_OUT_6") (pintype "bidirectional"))
    )
    (net (code "50") (name "PA0") (class "Default")
      (node (ref "U1") (pin "10") (pinfunction "PA0_WKUP_10") (pintype "bidirectional"))
    )
    (net (code "51") (name "PA8") (class "Default")
      (node (ref "U1") (pin "29") (pinfunction "PA8_29") (pintype "bidirectional"))
    )
    (net (code "52") (name "PA11") (class "Default")
      (node (ref "U1") (pin "32") (pinfunction "PA11_32") (pintype "bidirectional"))
    )
    (net (code "53") (name "PA12") (class "Default")
      (node (ref "U1") (pin "33") (pinfunction "PA12_33") (pintype "bidirectional"))
    )
    (net (code "54") (name "PA13") (class "Default")
      (node (ref "R5") (pin "2") (pinfunction "2_2") (pintype "passive"))
      (node (ref "U$3") (pin "3") (pinfunction "P$3_3") (pintype "bidirectional"))
      (node (ref "U1") (pin "34") (pinfunction "PA13_34") (pintype "bidirectional"))
    )
    (net (code "55") (name "PA14") (class "Default")
      (node (ref "R4") (pin "2") (pinfunction "2_2") (pintype "passive"))
      (node (ref "U$3") (pin "2") (pinfunction "P$2_2") (pintype "bidirectional"))
      (node (ref "U1") (pin "37") (pinfunction "PA14_37") (pintype "bidirectional"))
    )
    (net (code "56") (name "PA15") (class "Default")
      (node (ref "U1") (pin "38") (pinfunction "PA15_38") (pintype "bidirectional"))
    )
    (net (code "57") (name "PB3") (class "Default")
      (node (ref "U1") (pin "39") (pinfunction "PB3_39") (pintype "bidirectional"))
    )
    (net (code "58") (name "PB4") (class "Default")
      (node (ref "U1") (pin "40") (pinfunction "PB4_40") (pintype "bidirectional"))
    )
    (net (code "59") (name "PB5") (class "Default")
      (node (ref "U1") (pin "41") (pinfunction "PB5_41") (pintype "bidirectional"))
    )
    (net (code "60") (name "PB8") (class "Default")
      (node (ref "U1") (pin "45") (pinfunction "PB8_45") (pintype "bidirectional"))
    )
    (net (code "61") (name "PB9") (class "Default")
      (node (ref "U1") (pin "46") (pinfunction "PB9_46") (pintype "bidirectional"))
    )
    (net (code "62") (name "PB12") (class "Default")
      (node (ref "U$9") (pin "3") (pinfunction "P$3_3") (pintype "bidirectional"))
      (node (ref "U1") (pin "25") (pinfunction "PB12_25") (pintype "bidirectional"))
    )
    (net (code "63") (name "PB13") (class "Default")
      (node (ref "U$13") (pin "3") (pinfunction "P$3_3") (pintype "bidirectional"))
      (node (ref "U1") (pin "26") (pinfunction "PB13_26") (pintype "bidirectional"))
    )
    (net (code "64") (name "PB14") (class "Default")
      (node (ref "U$14") (pin "3") (pinfunction "P$3_3") (pintype "bidirectional"))
      (node (ref "U1") (pin "27") (pinfunction "PB14_27") (pintype "bidirectional"))
    )
    (net (code "65") (name "PB15") (class "Default")
      (node (ref "U$15") (pin "3") (pinfunction "P$3_3") (pintype "bidirectional"))
      (node (ref "U1") (pin "28") (pinfunction "PB15_28") (pintype "bidirectional"))
    )
    (net (code "66") (name "PC13") (class "Default")
      (node (ref "R21") (pin "2") (pinfunction "2_2") (pintype "passive"))
      (node (ref "U1") (pin "2") (pinfunction "PC13-TAMPER-RTC_2") (pintype "bidirectional"))
    )
    (net (code "67") (name "PC14") (class "Default")
      (node (ref "R14") (pin "2") (pinfunction "2_2") (pintype "passive"))
      (node (ref "U1") (pin "3") (pinfunction "PC14-OSC32_IN_3") (pintype "bidirectional"))
    )
    (net (code "68") (name "PC15") (class "Default")
      (node (ref "R23") (pin "2") (pinfunction "2_2") (pintype "passive"))
      (node (ref "U1") (pin "4") (pinfunction "PC15-OSC32_OUT_4") (pintype "bidirectional"))
    )
    (net (code "69") (name "RESET") (class "Default")
      (node (ref "U$8") (pin "5") (pinfunction "RESET_5") (pintype "input"))
    )
    (net (code "70") (name "RST") (class "Default")
      (node (ref "C1") (pin "1") (pinfunction "1_1") (pintype "passive"))
      (node (ref "R3") (pin "1") (pinfunction "1_1") (pintype "passive"))
      (node (ref "S1") (pin "2") (pinfunction "2_2") (pintype "passive"))
      (node (ref "U1") (pin "7") (pinfunction "NRST_7") (pintype "input"))
    )
    (net (code "71") (name "RX1") (class "Default")
      (node (ref "U$12") (pin "3") (pinfunction "P$3_3") (pintype "bidirectional"))
      (node (ref "U1") (pin "31") (pinfunction "PA10_31") (pintype "bidirectional"))
    )
    (net (code "72") (name "RX2") (class "Default")
      (node (ref "JMP6") (pin "3") (pinfunction "3_3") (pintype "passive"))
      (node (ref "JMP7") (pin "1") (pinfunction "1_1") (pintype "passive"))
      (node (ref "U$11") (pin "3") (pinfunction "P$3_3") (pintype "bidirectional"))
      (node (ref "U1") (pin "13") (pinfunction "PA3_13") (pintype "bidirectional"))
    )
    (net (code "73") (name "SCL1") (class "Default")
      (node (ref "JMP1") (pin "1") (pinfunction "1_1") (pintype "passive"))
      (node (ref "U1") (pin "42") (pinfunction "PB6_42") (pintype "bidirectional"))
    )
    (net (code "74") (name "SCL2{slash}TX3") (class "Default")
      (node (ref "JMP1") (pin "3") (pinfunction "3_3") (pintype "passive"))
      (node (ref "U$7") (pin "3") (pinfunction "P$3_3") (pintype "bidirectional"))
      (node (ref "U1") (pin "21") (pinfunction "PB10_21") (pintype "bidirectional"))
    )
    (net (code "75") (name "SDA1") (class "Default")
      (node (ref "JMP2") (pin "1") (pinfunction "1_1") (pintype "passive"))
      (node (ref "U1") (pin "43") (pinfunction "PB7_43") (pintype "bidirectional"))
    )
    (net (code "76") (name "SDA2{slash}RX3") (class "Default")
      (node (ref "JMP2") (pin "3") (pinfunction "3_3") (pintype "passive"))
      (node (ref "U$7") (pin "4") (pinfunction "P$4_4") (pintype "bidirectional"))
      (node (ref "U1") (pin "22") (pinfunction "PB11_22") (pintype "bidirectional"))
    )
    (net (code "77") (name "TX1") (class "Default")
      (node (ref "U$12") (pin "4") (pinfunction "P$4_4") (pintype "bidirectional"))
      (node (ref "U1") (pin "30") (pinfunction "PA9_30") (pintype "bidirectional"))
    )
    (net (code "78") (name "TX2") (class "Default")
      (node (ref "JMP6") (pin "1") (pinfunction "1_1") (pintype "passive"))
      (node (ref "JMP7") (pin "3") (pinfunction "3_3") (pintype "passive"))
      (node (ref "U$11") (pin "4") (pinfunction "P$4_4") (pintype "bidirectional"))
      (node (ref "U1") (pin "12") (pinfunction "PA2_12") (pintype "bidirectional"))
    )
    (net (code "79") (name "UL2") (class "Default")
      (node (ref "U1") (pin "14") (pinfunction "PA4_14") (pintype "bidirectional"))
      (node (ref "U3") (pin "2") (pinfunction "ZB_2") (pintype "bidirectional"))
    )
    (net (code "80") (name "UL3") (class "Default")
      (node (ref "U1") (pin "15") (pinfunction "PA5_15") (pintype "bidirectional"))
      (node (ref "U3") (pin "3") (pinfunction "SB_3") (pintype "bidirectional"))
    )
    (net (code "81") (name "VBAT") (class "Default")
      (node (ref "U1") (pin "1") (pinfunction "VBAT_1") (pintype "bidirectional"))
    )
    (net (code "82") (name "VCC") (class "Default")
      (node (ref "C12") (pin "+") (pinfunction "+_+") (pintype "passive"))
      (node (ref "C3") (pin "1") (pinfunction "1_1") (pintype "passive"))
      (node (ref "C4") (pin "1") (pinfunction "1_1") (pintype "passive"))
      (node (ref "C6") (pin "1") (pinfunction "1_1") (pintype "passive"))
      (node (ref "C7") (pin "+") (pinfunction "+_+") (pintype "passive"))
      (node (ref "JMP10") (pin "3") (pinfunction "3_3") (pintype "passive"))
      (node (ref "JMP5") (pin "3") (pinfunction "3_3") (pintype "passive"))
      (node (ref "JMP8") (pin "3") (pinfunction "3_3") (pintype "passive"))
      (node (ref "JMP9") (pin "3") (pinfunction "3_3") (pintype "passive"))
      (node (ref "R6") (pin "2") (pinfunction "2_2") (pintype "passive"))
      (node (ref "U4") (pin "3") (pinfunction "IN_3") (pintype "input"))
      (node (ref "U6") (pin "2") (pinfunction "OUT_2") (pintype "output"))
      (node (ref "U6") (pin "4") (pinfunction "4_4") (pintype "passive"))
    )
    (net (code "83") (name "VIN") (class "Default")
      (node (ref "C10") (pin "+") (pinfunction "+_+") (pintype "passive"))
      (node (ref "C14") (pin "+") (pinfunction "+_+") (pintype "passive"))
      (node (ref "C16") (pin "+") (pinfunction "+_+") (pintype "passive"))
      (node (ref "C18") (pin "+") (pinfunction "+_+") (pintype "passive"))
      (node (ref "C29") (pin "+") (pinfunction "+_+") (pintype "passive"))
      (node (ref "C9") (pin "1") (pinfunction "1_1") (pintype "passive"))
      (node (ref "D2") (pin "C") (pinfunction "C_C") (pintype "passive"))
      (node (ref "D4") (pin "C") (pinfunction "C_C") (pintype "passive"))
      (node (ref "D5") (pin "C") (pinfunction "C_C") (pintype "passive"))
      (node (ref "D6") (pin "C") (pinfunction "C_C") (pintype "passive"))
      (node (ref "D7") (pin "C") (pinfunction "C_C") (pintype "passive"))
      (node (ref "Q1") (pin "2") (pinfunction "S_2") (pintype "passive"))
      (node (ref "Q3") (pin "2") (pinfunction "S_2") (pintype "passive"))
      (node (ref "Q4") (pin "2") (pinfunction "S_2") (pintype "passive"))
      (node (ref "Q5") (pin "2") (pinfunction "S_2") (pintype "passive"))
      (node (ref "Q6") (pin "S") (pinfunction "S_S") (pintype "bidirectional"))
      (node (ref "R15") (pin "2") (pinfunction "2_2") (pintype "passive"))
      (node (ref "R17") (pin "2") (pinfunction "2_2") (pintype "passive"))
      (node (ref "R19") (pin "2") (pinfunction "2_2") (pintype "passive"))
      (node (ref "R40") (pin "2") (pinfunction "2_2") (pintype "passive"))
      (node (ref "R41") (pin "2") (pinfunction "2_2") (pintype "passive"))
      (node (ref "U$20") (pin "P$1") (pinfunction "1_P$1") (pintype "passive"))
      (node (ref "U$22") (pin "P$1") (pinfunction "1_P$1") (pintype "passive"))
      (node (ref "U3") (pin "9") (pinfunction "COM_9") (pintype "bidirectional"))
      (node (ref "U6") (pin "3") (pinfunction "IN_3") (pintype "input"))
    )
    (net (code "84") (name "unconnected-(J1-Pad5)") (class "Default")
      (node (ref "J1") (pin "5") (pinfunction "5_5") (pintype "passive"))
    )
    (net (code "85") (name "unconnected-(J1-Pad6)") (class "Default")
      (node (ref "J1") (pin "6") (pinfunction "6_6") (pintype "passive"))
    )
    (net (code "86") (name "unconnected-(J2-Pad5)") (class "Default")
      (node (ref "J2") (pin "5") (pinfunction "5_5") (pintype "passive"))
    )
    (net (code "87") (name "unconnected-(J2-Pad6)") (class "Default")
      (node (ref "J2") (pin "6") (pinfunction "6_6") (pintype "passive"))
    )
    (net (code "88") (name "unconnected-(J2-Pad7)") (class "Default")
      (node (ref "J2") (pin "7") (pinfunction "7_7") (pintype "passive"))
    )
    (net (code "89") (name "unconnected-(J2-Pad8)") (class "Default")
      (node (ref "J2") (pin "8") (pinfunction "8_8") (pintype "passive"))
    )
    (net (code "90") (name "unconnected-(U$8-AD0{slash}DIO0-Pad20)") (class "Default")
      (node (ref "U$8") (pin "20") (pinfunction "AD0/DIO0_20") (pintype "bidirectional"))
    )
    (net (code "91") (name "unconnected-(U$8-AD1{slash}DIO1-Pad19)") (class "Default")
      (node (ref "U$8") (pin "19") (pinfunction "AD1/DIO1_19") (pintype "bidirectional"))
    )
    (net (code "92") (name "unconnected-(U$8-AD2{slash}DIO2-Pad18)") (class "Default")
      (node (ref "U$8") (pin "18") (pinfunction "AD2/DIO2_18") (pintype "bidirectional"))
    )
    (net (code "93") (name "unconnected-(U$8-AD3{slash}DIO3-Pad17)") (class "Default")
      (node (ref "U$8") (pin "17") (pinfunction "AD3/DIO3_17") (pintype "bidirectional"))
    )
    (net (code "94") (name "unconnected-(U$8-AD4{slash}DIO4-Pad11)") (class "Default")
      (node (ref "U$8") (pin "11") (pinfunction "AD4/DIO4_11") (pintype "bidirectional"))
    )
    (net (code "95") (name "unconnected-(U$8-ASC{slash}AD5{slash}DIO5-Pad15)") (class "Default")
      (node (ref "U$8") (pin "15") (pinfunction "ASC/AD5/DIO5_15") (pintype "bidirectional"))
    )
    (net (code "96") (name "unconnected-(U$8-CTS{slash}DIO7-Pad12)") (class "Default")
      (node (ref "U$8") (pin "12") (pinfunction "CTS/DIO7_12") (pintype "bidirectional"))
    )
    (net (code "97") (name "unconnected-(U$8-DO8-Pad4)") (class "Default")
      (node (ref "U$8") (pin "4") (pinfunction "DO8_4") (pintype "output"))
    )
    (net (code "98") (name "unconnected-(U$8-DTR{slash}DI8-Pad9)") (class "Default")
      (node (ref "U$8") (pin "9") (pinfunction "DTR/DI8_9") (pintype "input"))
    )
    (net (code "99") (name "unconnected-(U$8-ON{slash}SLEEP-Pad13)") (class "Default")
      (node (ref "U$8") (pin "13") (pinfunction "ON/SLEEP_13") (pintype "output"))
    )
    (net (code "100") (name "unconnected-(U$8-PWM0{slash}RSSI-Pad6)") (class "Default")
      (node (ref "U$8") (pin "6") (pinfunction "PWM0/RSSI_6") (pintype "output"))
    )
    (net (code "101") (name "unconnected-(U$8-PWM1-Pad7)") (class "Default")
      (node (ref "U$8") (pin "7") (pinfunction "PWM1_7") (pintype "output"))
    )
    (net (code "102") (name "unconnected-(U$8-RESERVED-Pad8)") (class "Default")
      (node (ref "U$8") (pin "8") (pinfunction "RESERVED_8") (pintype "no_connect"))
    )
    (net (code "103") (name "unconnected-(U$8-RTS{slash}AD6{slash}DIO6-Pad16)") (class "Default")
      (node (ref "U$8") (pin "16") (pinfunction "RTS/AD6/DIO6_16") (pintype "bidirectional"))
    )
    (net (code "104") (name "unconnected-(U$8-VREF-Pad14)") (class "Default")
      (node (ref "U$8") (pin "14") (pinfunction "VREF_14") (pintype "input"))
    )
  )
)
